# ProMicro_Attniy85_Prog.net
KiCad netlist of a schematic drawn in EAGLE
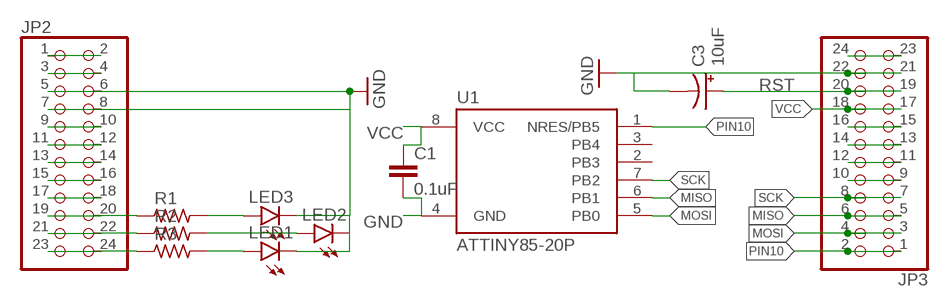
[diagram p0: schematic, sheet 1]

(export (version "E")
  (design (tool "Eeschema 10.0.6"))
  (components
    (comp (ref "C1")
      (value "0.1uF")
      (footprint "eagle-import:0603")
      (libsource (lib "eagle-import") (part "0.1UF-0603-100V-10%"))
    )
    (comp (ref "C3")
      (value "10uF")
      (footprint "eagle-import:EIA3216")
      (libsource (lib "eagle-import") (part "10UF-POLAR-EIA3216-16V-10%(TANT)"))
    )
    (comp (ref "JP2")
      (value "PINHD-2X12")
      (footprint "eagle-import:2X12")
      (libsource (lib "eagle-import") (part "PINHD-2X12"))
    )
    (comp (ref "JP3")
      (value "PINHD-2X12")
      (footprint "eagle-import:2X12")
      (libsource (lib "eagle-import") (part "PINHD-2X12"))
    )
    (comp (ref "LED1")
      (value "LEDCHIP-LED0805")
      (footprint "eagle-import:CHIP-LED0805")
      (libsource (lib "eagle-import") (part "LEDCHIP-LED0805"))
    )
    (comp (ref "LED2")
      (value "LEDCHIP-LED0805")
      (footprint "eagle-import:CHIP-LED0805")
      (libsource (lib "eagle-import") (part "LEDCHIP-LED0805"))
    )
    (comp (ref "LED3")
      (value "LEDCHIP-LED0805")
      (footprint "eagle-import:CHIP-LED0805")
      (libsource (lib "eagle-import") (part "LEDCHIP-LED0805"))
    )
    (comp (ref "R1")
      (value "R_0805")
      (footprint "eagle-import:R0805")
      (libsource (lib "eagle-import") (part "R_0805"))
    )
    (comp (ref "R2")
      (value "R_0805")
      (footprint "eagle-import:R0805")
      (libsource (lib "eagle-import") (part "R_0805"))
    )
    (comp (ref "R3")
      (value "R_0805")
      (footprint "eagle-import:R0805")
      (libsource (lib "eagle-import") (part "R_0805"))
    )
    (comp (ref "U1")
      (value "ATTINY85-20P")
      (footprint "eagle-import:PDIP08_300MIL")
      (libsource (lib "eagle-import") (part "ATTINY85P-20"))
    )
  )
  (nets
    (net (code "1") (name "/RST") (class "Default")
      (node (ref "C3") (pin "+") (pinfunction "+_+") (pintype "passive"))
      (node (ref "JP3") (pin "19") (pinfunction "19_19") (pintype "passive"))
      (node (ref "JP3") (pin "20") (pinfunction "20_20") (pintype "passive"))
    )
    (net (code "2") (name "GND") (class "Default")
      (node (ref "C1") (pin "2") (pinfunction "2_2") (pintype "passive"))
      (node (ref "C3") (pin "-") (pinfunction "-_-") (pintype "passive"))
      (node (ref "JP2") (pin "5") (pinfunction "5_5") (pintype "passive"))
      (node (ref "JP2") (pin "6") (pinfunction "6_6") (pintype "passive"))
      (node (ref "JP2") (pin "7") (pinfunction "7_7") (pintype "passive"))
      (node (ref "JP2") (pin "8") (pinfunction "8_8") (pintype "passive"))
      (node (ref "JP3") (pin "21") (pinfunction "21_21") (pintype "passive"))
      (node (ref "JP3") (pin "22") (pinfunction "22_22") (pintype "passive"))
      (node (ref "LED1") (pin "C") (pinfunction "C_C") (pintype "passive"))
      (node (ref "LED2") (pin "C") (pinfunction "C_C") (pintype "passive"))
      (node (ref "LED3") (pin "C") (pinfunction "C_C") (pintype "passive"))
      (node (ref "U1") (pin "4") (pinfunction "GND_4") (pintype "power_in"))
    )
    (net (code "3") (name "MISO") (class "Default")
      (node (ref "JP3") (pin "5") (pinfunction "5_5") (pintype "passive"))
      (node (ref "JP3") (pin "6") (pinfunction "6_6") (pintype "passive"))
      (node (ref "U1") (pin "6") (pinfunction "PB1_6") (pintype "bidirectional"))
    )
    (net (code "4") (name "MOSI") (class "Default")
      (node (ref "JP3") (pin "3") (pinfunction "3_3") (pintype "passive"))
      (node (ref "JP3") (pin "4") (pinfunction "4_4") (pintype "passive"))
      (node (ref "U1") (pin "5") (pinfunction "PB0_5") (pintype "bidirectional"))
    )
    (net (code "5") (name "Net-(JP2-Pad1)") (class "Default")
      (node (ref "JP2") (pin "1") (pinfunction "1_1") (pintype "passive"))
      (node (ref "JP2") (pin "2") (pinfunction "2_2") (pintype "passive"))
    )
    (net (code "6") (name "Net-(JP2-Pad3)") (class "Default")
      (node (ref "JP2") (pin "3") (pinfunction "3_3") (pintype "passive"))
      (node (ref "JP2") (pin "4") (pinfunction "4_4") (pintype "passive"))
    )
    (net (code "7") (name "Net-(JP2-Pad10)") (class "Default")
      (node (ref "JP2") (pin "10") (pinfunction "10_10") (pintype "passive"))
      (node (ref "JP2") (pin "9") (pinfunction "9_9") (pintype "passive"))
    )
    (net (code "8") (name "Net-(JP2-Pad11)") (class "Default")
      (node (ref "JP2") (pin "11") (pinfunction "11_11") (pintype "passive"))
      (node (ref "JP2") (pin "12") (pinfunction "12_12") (pintype "passive"))
    )
    (net (code "9") (name "Net-(JP2-Pad13)") (class "Default")
      (node (ref "JP2") (pin "13") (pinfunction "13_13") (pintype "passive"))
      (node (ref "JP2") (pin "14") (pinfunction "14_14") (pintype "passive"))
    )
    (net (code "10") (name "Net-(JP2-Pad15)") (class "Default")
      (node (ref "JP2") (pin "15") (pinfunction "15_15") (pintype "passive"))
      (node (ref "JP2") (pin "16") (pinfunction "16_16") (pintype "passive"))
    )
    (net (code "11") (name "Net-(JP2-Pad17)") (class "Default")
      (node (ref "JP2") (pin "17") (pinfunction "17_17") (pintype "passive"))
      (node (ref "JP2") (pin "18") (pinfunction "18_18") (pintype "passive"))
    )
    (net (code "12") (name "Net-(JP2-Pad19)") (class "Default")
      (node (ref "JP2") (pin "19") (pinfunction "19_19") (pintype "passive"))
      (node (ref "JP2") (pin "20") (pinfunction "20_20") (pintype "passive"))
      (node (ref "R1") (pin "1") (pinfunction "1_1") (pintype "passive"))
    )
    (net (code "13") (name "Net-(JP2-Pad21)") (class "Default")
      (node (ref "JP2") (pin "21") (pinfunction "21_21") (pintype "passive"))
      (node (ref "JP2") (pin "22") (pinfunction "22_22") (pintype "passive"))
      (node (ref "R2") (pin "1") (pinfunction "1_1") (pintype "passive"))
    )
    (net (code "14") (name "Net-(JP2-Pad23)") (class "Default")
      (node (ref "JP2") (pin "23") (pinfunction "23_23") (pintype "passive"))
      (node (ref "JP2") (pin "24") (pinfunction "24_24") (pintype "passive"))
      (node (ref "R3") (pin "1") (pinfunction "1_1") (pintype "passive"))
    )
    (net (code "15") (name "Net-(JP3-Pad10)") (class "Default")
      (node (ref "JP3") (pin "10") (pinfunction "10_10") (pintype "passive"))
      (node (ref "JP3") (pin "9") (pinfunction "9_9") (pintype "passive"))
    )
    (net (code "16") (name "Net-(JP3-Pad11)") (class "Default")
      (node (ref "JP3") (pin "11") (pinfunction "11_11") (pintype "passive"))
      (node (ref "JP3") (pin "12") (pinfunction "12_12") (pintype "passive"))
    )
    (net (code "17") (name "Net-(JP3-Pad13)") (class "Default")
      (node (ref "JP3") (pin "13") (pinfunction "13_13") (pintype "passive"))
      (node (ref "JP3") (pin "14") (pinfunction "14_14") (pintype "passive"))
    )
    (net (code "18") (name "Net-(JP3-Pad15)") (class "Default")
      (node (ref "JP3") (pin "15") (pinfunction "15_15") (pintype "passive"))
      (node (ref "JP3") (pin "16") (pinfunction "16_16") (pintype "passive"))
    )
    (net (code "19") (name "Net-(JP3-Pad23)") (class "Default")
      (node (ref "JP3") (pin "23") (pinfunction "23_23") (pintype "passive"))
      (node (ref "JP3") (pin "24") (pinfunction "24_24") (pintype "passive"))
    )
    (net (code "20") (name "Net-(LED1-PadA)") (class "Default")
      (node (ref "LED1") (pin "A") (pinfunction "A_A") (pintype "passive"))
      (node (ref "R3") (pin "2") (pinfunction "2_2") (pintype "passive"))
    )
    (net (code "21") (name "Net-(LED2-PadA)") (class "Default")
      (node (ref "LED2") (pin "A") (pinfunction "A_A") (pintype "passive"))
      (node (ref "R2") (pin "2") (pinfunction "2_2") (pintype "passive"))
    )
    (net (code "22") (name "Net-(LED3-PadA)") (class "Default")
      (node (ref "LED3") (pin "A") (pinfunction "A_A") (pintype "passive"))
      (node (ref "R1") (pin "2") (pinfunction "2_2") (pintype "passive"))
    )
    (net (code "23") (name "PIN10") (class "Default")
      (node (ref "JP3") (pin "1") (pinfunction "1_1") (pintype "passive"))
      (node (ref "JP3") (pin "2") (pinfunction "2_2") (pintype "passive"))
      (node (ref "U1") (pin "1") (pinfunction "NRES/PB5_1") (pintype "bidirectional"))
    )
    (net (code "24") (name "SCK") (class "Default")
      (node (ref "JP3") (pin "7") (pinfunction "7_7") (pintype "passive"))
      (node (ref "JP3") (pin "8") (pinfunction "8_8") (pintype "passive"))
      (node (ref "U1") (pin "7") (pinfunction "PB2_7") (pintype "bidirectional"))
    )
    (net (code "25") (name "VCC") (class "Default")
      (node (ref "C1") (pin "1") (pinfunction "1_1") (pintype "passive"))
      (node (ref "JP3") (pin "17") (pinfunction "17_17") (pintype "passive"))
      (node (ref "JP3") (pin "18") (pinfunction "18_18") (pintype "passive"))
      (node (ref "U1") (pin "8") (pinfunction "VCC_8") (pintype "power_in"))
    )
    (net (code "26") (name "unconnected-(U1-PB3-Pad2)") (class "Default")
      (node (ref "U1") (pin "2") (pinfunction "PB3_2") (pintype "bidirectional"))
    )
    (net (code "27") (name "unconnected-(U1-PB4-Pad3)") (class "Default")
      (node (ref "U1") (pin "3") (pinfunction "PB4_3") (pintype "bidirectional"))
    )
  )
)
